# laser_buck_driver.net
KiCad netlist of a schematic drawn in EAGLE
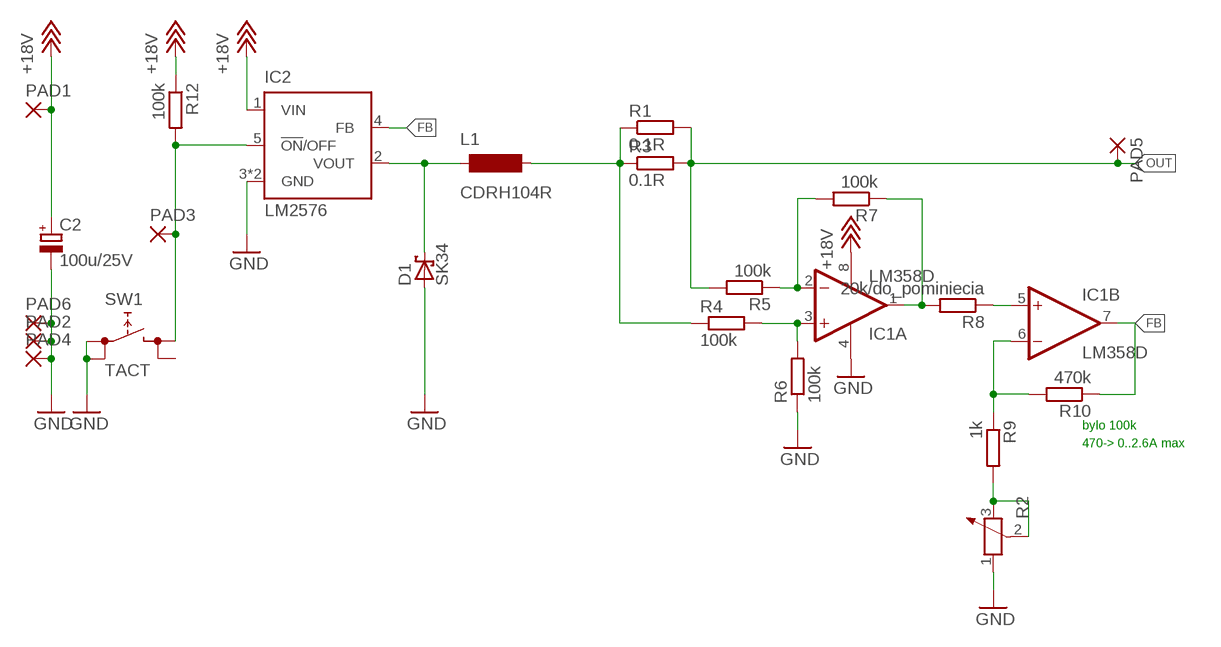
[diagram p0: schematic, sheet 1]

(export (version "E")
  (design (tool "Eeschema 10.0.6"))
  (components
    (comp (ref "C2")
      (value "100u/25V")
      (footprint "eagle-import:153CLV-0810")
      (libsource (lib "eagle-import") (part "CPOL-EU153CLV-0810"))
    )
    (comp (ref "D1")
      (value "SK34")
      (footprint "eagle-import:SMA(DO214-AC)")
      (libsource (lib "eagle-import") (part "SK34"))
    )
    (comp (ref "IC1")
      (value "LM358D")
      (footprint "eagle-import:SO08")
      (libsource (lib "eagle-import") (part "LM358D"))
    )
    (comp (ref "IC2")
      (value "LM2576")
      (footprint "eagle-import:TO263-5")
      (libsource (lib "eagle-import") (part "LM2576"))
    )
    (comp (ref "L1")
      (value "CDRH104R")
      (footprint "eagle-import:CDRH104-R")
      (libsource (lib "eagle-import") (part "CDRH104R"))
    )
    (comp (ref "PAD1")
      (value "SMD2")
      (footprint "eagle-import:SMD1,27-2,54")
      (libsource (lib "eagle-import") (part "SMD2"))
    )
    (comp (ref "PAD2")
      (value "SMD2")
      (footprint "eagle-import:SMD1,27-2,54")
      (libsource (lib "eagle-import") (part "SMD2"))
    )
    (comp (ref "PAD3")
      (value "SMD2")
      (footprint "eagle-import:SMD1,27-2,54")
      (libsource (lib "eagle-import") (part "SMD2"))
    )
    (comp (ref "PAD4")
      (value "SMD2")
      (footprint "eagle-import:SMD1,27-2,54")
      (libsource (lib "eagle-import") (part "SMD2"))
    )
    (comp (ref "PAD5")
      (value "SMD2")
      (footprint "eagle-import:SMD1,27-2,54")
      (libsource (lib "eagle-import") (part "SMD2"))
    )
    (comp (ref "PAD6")
      (value "SMD2")
      (footprint "eagle-import:SMD1,27-2,54")
      (libsource (lib "eagle-import") (part "SMD2"))
    )
    (comp (ref "R1")
      (value "0.1R")
      (footprint "eagle-import:R1206")
      (libsource (lib "eagle-import") (part "R-EU_R1206"))
    )
    (comp (ref "R2")
      (value "POTENTIOMETER_")
      (footprint "eagle-import:RTRIM_SMD_CUSTOM")
      (libsource (lib "eagle-import") (part "POTENTIOMETER_"))
    )
    (comp (ref "R3")
      (value "0.1R")
      (footprint "eagle-import:R1206")
      (libsource (lib "eagle-import") (part "R-EU_R1206"))
    )
    (comp (ref "R4")
      (value "100k")
      (footprint "eagle-import:R0805")
      (libsource (lib "eagle-import") (part "R-EU_R0805"))
    )
    (comp (ref "R5")
      (value "100k")
      (footprint "eagle-import:R0805")
      (libsource (lib "eagle-import") (part "R-EU_R0805"))
    )
    (comp (ref "R6")
      (value "100k")
      (footprint "eagle-import:R0805")
      (libsource (lib "eagle-import") (part "R-EU_R0805"))
    )
    (comp (ref "R7")
      (value "100k")
      (footprint "eagle-import:R0805")
      (libsource (lib "eagle-import") (part "R-EU_R0805"))
    )
    (comp (ref "R8")
      (value "20k/do_pominiecia")
      (footprint "eagle-import:R0805")
      (libsource (lib "eagle-import") (part "R-EU_R0805"))
    )
    (comp (ref "R9")
      (value "1k")
      (footprint "eagle-import:R0805")
      (libsource (lib "eagle-import") (part "R-EU_R0805"))
    )
    (comp (ref "R10")
      (value "470k")
      (footprint "eagle-import:R0805")
      (libsource (lib "eagle-import") (part "R-EU_R0805"))
    )
    (comp (ref "R12")
      (value "100k")
      (footprint "eagle-import:R1206")
      (libsource (lib "eagle-import") (part "resistor_R-EU_R1206"))
    )
    (comp (ref "SW1")
      (value "TACT")
      (footprint "eagle-import:TACT")
      (libsource (lib "eagle-import") (part "TACT"))
    )
  )
  (nets
    (net (code "1") (name "+18V") (class "Default")
      (node (ref "C2") (pin "+") (pinfunction "+_+") (pintype "passive"))
      (node (ref "IC1") (pin "8") (pinfunction "V+_8") (pintype "power_in"))
      (node (ref "IC2") (pin "1") (pinfunction "VIN_1") (pintype "input"))
      (node (ref "PAD1") (pin "1") (pinfunction "P_1") (pintype "passive"))
      (node (ref "R12") (pin "1") (pinfunction "1_1") (pintype "passive"))
    )
    (net (code "2") (name "FB") (class "Default")
      (node (ref "IC1") (pin "7") (pinfunction "OUT_7") (pintype "output"))
      (node (ref "IC2") (pin "4") (pinfunction "FB_4") (pintype "output"))
      (node (ref "R10") (pin "1") (pinfunction "1_1") (pintype "passive"))
    )
    (net (code "3") (name "GND") (class "Default")
      (node (ref "C2") (pin "-") (pinfunction "-_-") (pintype "passive"))
      (node (ref "D1") (pin "A") (pinfunction "A_A") (pintype "passive"))
      (node (ref "IC1") (pin "4") (pinfunction "V-_4") (pintype "power_in"))
      (node (ref "IC2") (pin "3") (pinfunction "GND_3") (pintype "power_in"))
      (node (ref "IC2") (pin "6") (pinfunction "GND_6") (pintype "power_in"))
      (node (ref "PAD2") (pin "1") (pinfunction "P_1") (pintype "passive"))
      (node (ref "PAD4") (pin "1") (pinfunction "P_1") (pintype "passive"))
      (node (ref "PAD6") (pin "1") (pinfunction "P_1") (pintype "passive"))
      (node (ref "R2") (pin "1") (pinfunction "1_1") (pintype "passive"))
      (node (ref "R6") (pin "1") (pinfunction "1_1") (pintype "passive"))
      (node (ref "SW1") (pin "1") (pinfunction "1_1") (pintype "passive"))
      (node (ref "SW1") (pin "4") (pinfunction "4_4") (pintype "passive"))
    )
    (net (code "4") (name "Net-(IC1A-+IN)") (class "Default")
      (node (ref "IC1") (pin "3") (pinfunction "+IN_3") (pintype "input"))
      (node (ref "R4") (pin "2") (pinfunction "2_2") (pintype "passive"))
      (node (ref "R6") (pin "2") (pinfunction "2_2") (pintype "passive"))
    )
    (net (code "5") (name "Net-(IC1A--IN)") (class "Default")
      (node (ref "IC1") (pin "2") (pinfunction "-IN_2") (pintype "input"))
      (node (ref "R5") (pin "1") (pinfunction "1_1") (pintype "passive"))
      (node (ref "R7") (pin "2") (pinfunction "2_2") (pintype "passive"))
    )
    (net (code "6") (name "Net-(IC1A-OUT)") (class "Default")
      (node (ref "IC1") (pin "1") (pinfunction "OUT_1") (pintype "output"))
      (node (ref "R7") (pin "1") (pinfunction "1_1") (pintype "passive"))
      (node (ref "R8") (pin "2") (pinfunction "2_2") (pintype "passive"))
    )
    (net (code "7") (name "Net-(IC1B-+IN)") (class "Default")
      (node (ref "IC1") (pin "5") (pinfunction "+IN_5") (pintype "input"))
      (node (ref "R8") (pin "1") (pinfunction "1_1") (pintype "passive"))
    )
    (net (code "8") (name "Net-(IC1B--IN)") (class "Default")
      (node (ref "IC1") (pin "6") (pinfunction "-IN_6") (pintype "input"))
      (node (ref "R10") (pin "2") (pinfunction "2_2") (pintype "passive"))
      (node (ref "R9") (pin "1") (pinfunction "1_1") (pintype "passive"))
    )
    (net (code "9") (name "Net-(IC2-VOUT)") (class "Default")
      (node (ref "D1") (pin "C") (pinfunction "C_C") (pintype "passive"))
      (node (ref "IC2") (pin "2") (pinfunction "VOUT_2") (pintype "passive"))
      (node (ref "L1") (pin "1") (pinfunction "1_1") (pintype "passive"))
    )
    (net (code "10") (name "Net-(IC2-~{ON}{slash}OFF)") (class "Default")
      (node (ref "IC2") (pin "5") (pinfunction "~{ON}/OFF_5") (pintype "input"))
      (node (ref "PAD3") (pin "1") (pinfunction "P_1") (pintype "passive"))
      (node (ref "R12") (pin "2") (pinfunction "2_2") (pintype "passive"))
      (node (ref "SW1") (pin "2") (pinfunction "2_2") (pintype "passive"))
    )
    (net (code "11") (name "Net-(L1-Pad2)") (class "Default")
      (node (ref "L1") (pin "2") (pinfunction "2_2") (pintype "passive"))
      (node (ref "R1") (pin "1") (pinfunction "1_1") (pintype "passive"))
      (node (ref "R3") (pin "1") (pinfunction "1_1") (pintype "passive"))
      (node (ref "R4") (pin "1") (pinfunction "1_1") (pintype "passive"))
    )
    (net (code "12") (name "Net-(R2-2)") (class "Default")
      (node (ref "R2") (pin "2") (pinfunction "3_2") (pintype "passive"))
      (node (ref "R2") (pin "3") (pinfunction "2_3") (pintype "passive"))
      (node (ref "R9") (pin "2") (pinfunction "2_2") (pintype "passive"))
    )
    (net (code "13") (name "OUT") (class "Default")
      (node (ref "PAD5") (pin "1") (pinfunction "P_1") (pintype "passive"))
      (node (ref "R1") (pin "2") (pinfunction "2_2") (pintype "passive"))
      (node (ref "R3") (pin "2") (pinfunction "2_2") (pintype "passive"))
      (node (ref "R5") (pin "2") (pinfunction "2_2") (pintype "passive"))
    )
    (net (code "14") (name "unconnected-(SW1-Pad3)") (class "Default")
      (node (ref "SW1") (pin "3") (pinfunction "3_3") (pintype "passive"))
    )
  )
)
